# canbus-nic.net
KiCad netlist of a schematic drawn in EAGLE
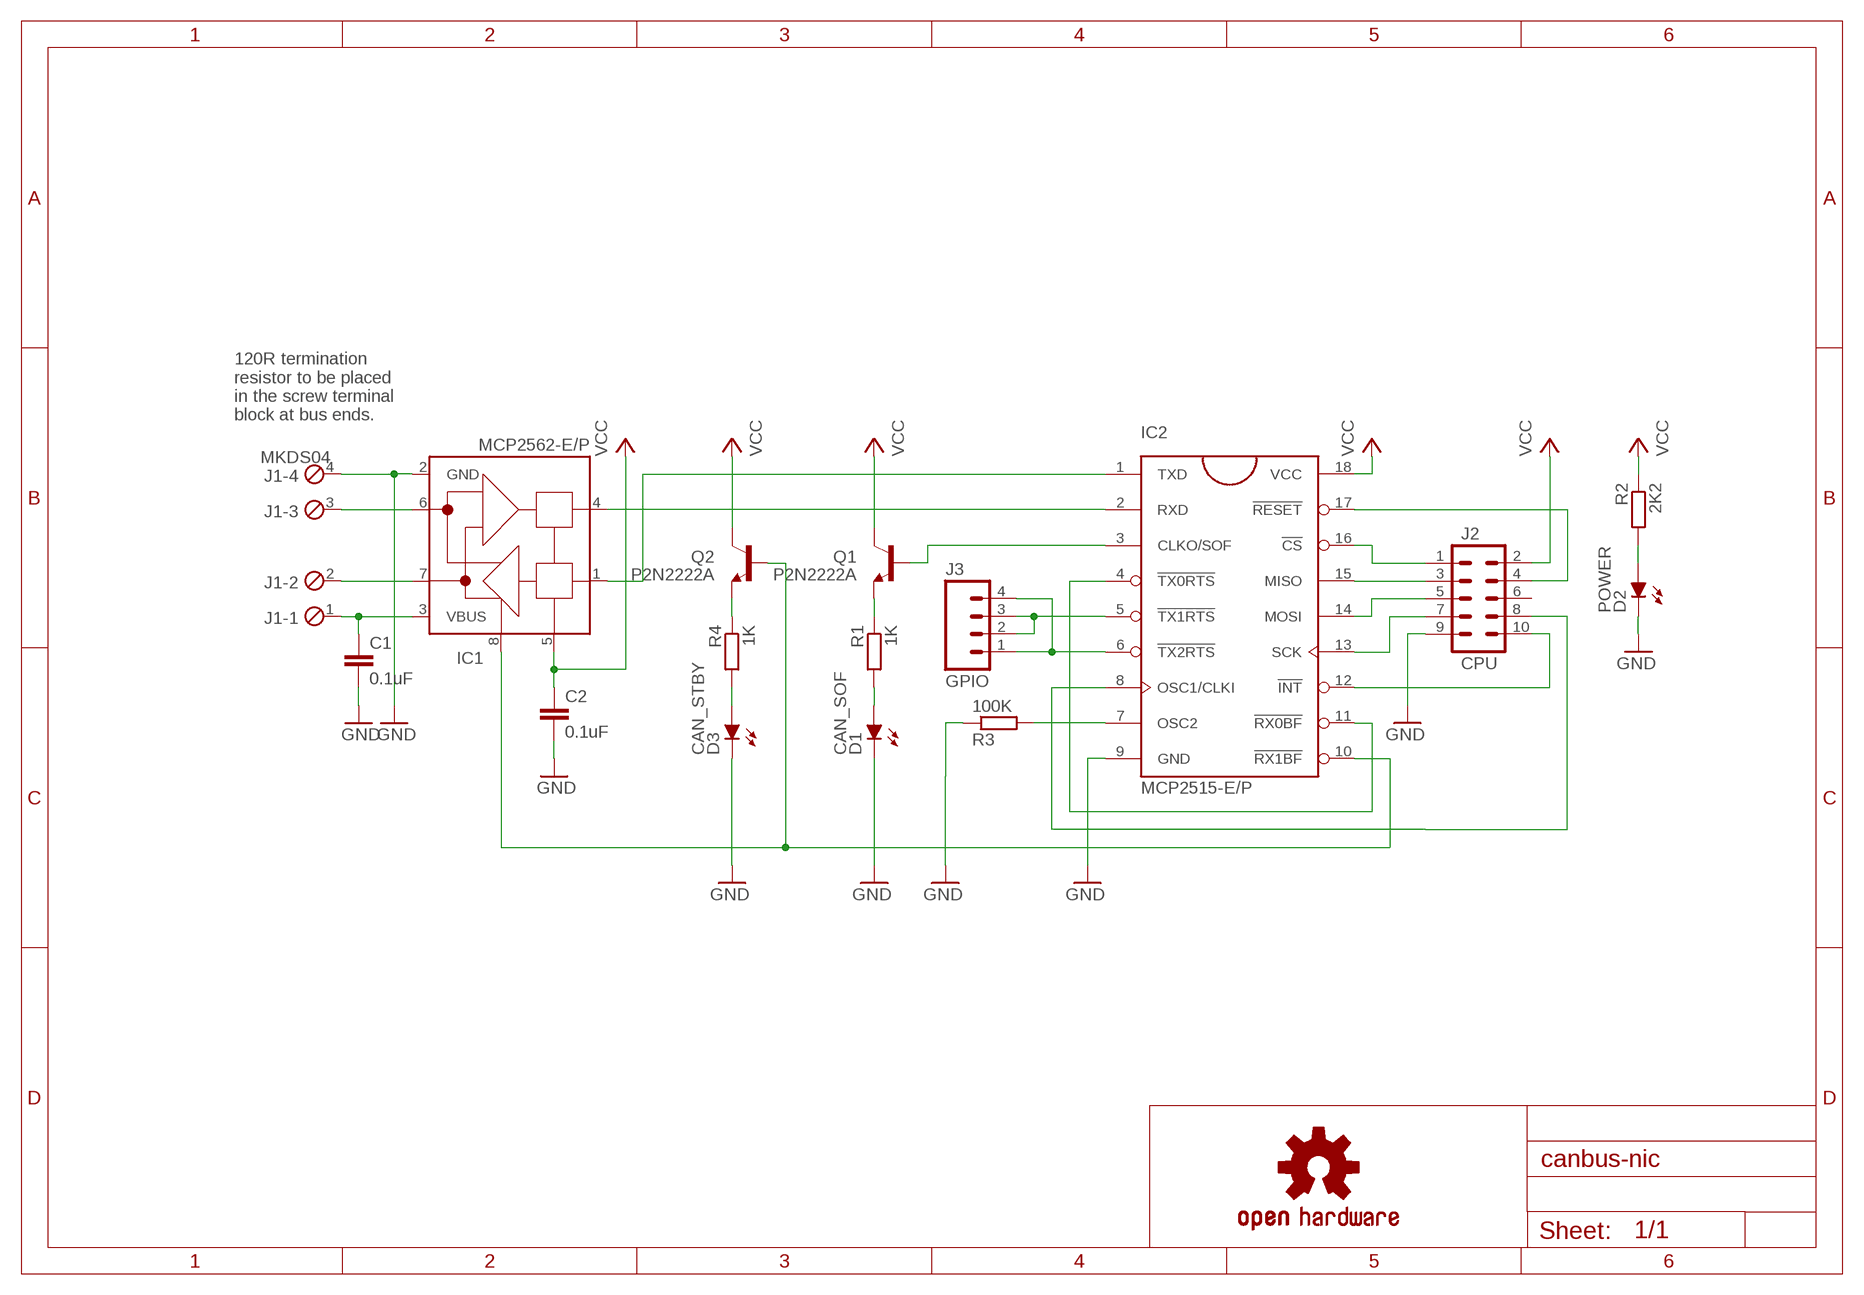
[diagram p0: schematic, sheet 1]

(export (version "E")
  (design (tool "Eeschema 10.0.6"))
  (components
    (comp (ref "C1")
      (value "0.1uF")
      (footprint "eagle-import:C050-025X075")
      (libsource (lib "eagle-import") (part "C-EU050-025X075"))
    )
    (comp (ref "C2")
      (value "0.1uF")
      (footprint "eagle-import:C050-025X075")
      (libsource (lib "eagle-import") (part "C-EU050-025X075"))
    )
    (comp (ref "D1")
      (value "CAN_SOF")
      (footprint "eagle-import:LED3MM")
      (libsource (lib "eagle-import") (part "LED3MM"))
    )
    (comp (ref "D2")
      (value "POWER")
      (footprint "eagle-import:LED3MM")
      (libsource (lib "eagle-import") (part "LED3MM"))
    )
    (comp (ref "D3")
      (value "CAN_STBY")
      (footprint "eagle-import:LED3MM")
      (libsource (lib "eagle-import") (part "LED3MM"))
    )
    (comp (ref "IC1")
      (value "MCP2562-E/P")
      (footprint "eagle-import:DIL08")
      (libsource (lib "eagle-import") (part "MCP2562-/PE"))
    )
    (comp (ref "IC2")
      (value "MCP2515-E/P")
      (footprint "eagle-import:DIL18")
      (libsource (lib "eagle-import") (part "MCP2515-/PE"))
    )
    (comp (ref "J1")
      (value "MKDS04")
      (footprint "eagle-import:MKDS04")
      (libsource (lib "eagle-import") (part "MKDS04"))
    )
    (comp (ref "J2")
      (value "CPU")
      (footprint "eagle-import:2X5-SHROUDED")
      (libsource (lib "eagle-import") (part "M05X2SHD"))
    )
    (comp (ref "J3")
      (value "GPIO")
      (footprint "eagle-import:1X04")
      (libsource (lib "eagle-import") (part "M04PTH"))
    )
    (comp (ref "LOGO1")
      (value "OSHW-LOGOMINI")
      (footprint "eagle-import:OSHW-LOGO-MINI")
      (libsource (lib "eagle-import") (part "OSHW-LOGOMINI"))
    )
    (comp (ref "Q1")
      (value "P2N2222A")
      (footprint "eagle-import:TO92")
      (libsource (lib "eagle-import") (part "P2N2222A"))
    )
    (comp (ref "Q2")
      (value "P2N2222A")
      (footprint "eagle-import:TO92")
      (libsource (lib "eagle-import") (part "P2N2222A"))
    )
    (comp (ref "R1")
      (value "1K")
      (footprint "eagle-import:0207_5V")
      (libsource (lib "eagle-import") (part "R-EU_0207/5V"))
    )
    (comp (ref "R2")
      (value "2K2")
      (footprint "eagle-import:0207_5V")
      (libsource (lib "eagle-import") (part "R-EU_0207/5V"))
    )
    (comp (ref "R3")
      (value "100K")
      (footprint "eagle-import:0207_5V")
      (libsource (lib "eagle-import") (part "R-EU_0207/5V"))
    )
    (comp (ref "R4")
      (value "1K")
      (footprint "eagle-import:0207_5V")
      (libsource (lib "eagle-import") (part "R-EU_0207/5V"))
    )
  )
  (nets
    (net (code "1") (name "GND") (class "Default")
      (node (ref "C1") (pin "2") (pinfunction "2_2") (pintype "passive"))
      (node (ref "C2") (pin "2") (pinfunction "2_2") (pintype "passive"))
      (node (ref "D1") (pin "K") (pinfunction "C_K") (pintype "passive"))
      (node (ref "D2") (pin "K") (pinfunction "C_K") (pintype "passive"))
      (node (ref "D3") (pin "K") (pinfunction "C_K") (pintype "passive"))
      (node (ref "IC1") (pin "2") (pinfunction "GND_2") (pintype "power_in"))
      (node (ref "IC2") (pin "9") (pinfunction "GND_9") (pintype "power_in"))
      (node (ref "J1") (pin "4") (pinfunction "1_4") (pintype "passive"))
      (node (ref "J2") (pin "9") (pinfunction "9_9") (pintype "passive"))
      (node (ref "R3") (pin "1") (pinfunction "1_1") (pintype "passive"))
    )
    (net (code "2") (name "Net-(D1-PadA)") (class "Default")
      (node (ref "D1") (pin "A") (pinfunction "A_A") (pintype "passive"))
      (node (ref "R1") (pin "2") (pinfunction "2_2") (pintype "passive"))
    )
    (net (code "3") (name "Net-(D2-PadA)") (class "Default")
      (node (ref "D2") (pin "A") (pinfunction "A_A") (pintype "passive"))
      (node (ref "R2") (pin "2") (pinfunction "2_2") (pintype "passive"))
    )
    (net (code "4") (name "Net-(D3-PadA)") (class "Default")
      (node (ref "D3") (pin "A") (pinfunction "A_A") (pintype "passive"))
      (node (ref "R4") (pin "2") (pinfunction "2_2") (pintype "passive"))
    )
    (net (code "5") (name "Net-(IC1-CANH)") (class "Default")
      (node (ref "IC1") (pin "7") (pinfunction "CANH_7") (pintype "bidirectional"))
      (node (ref "J1") (pin "2") (pinfunction "1_2") (pintype "passive"))
    )
    (net (code "6") (name "Net-(IC1-CANL)") (class "Default")
      (node (ref "IC1") (pin "6") (pinfunction "CANL_6") (pintype "bidirectional"))
      (node (ref "J1") (pin "3") (pinfunction "1_3") (pintype "passive"))
    )
    (net (code "7") (name "Net-(IC1-RXD)") (class "Default")
      (node (ref "IC1") (pin "4") (pinfunction "RXD_4") (pintype "output"))
      (node (ref "IC2") (pin "2") (pinfunction "RXD_2") (pintype "input"))
    )
    (net (code "8") (name "Net-(IC1-STBY)") (class "Default")
      (node (ref "IC1") (pin "8") (pinfunction "STBY_8") (pintype "input"))
      (node (ref "IC2") (pin "10") (pinfunction "~{RX1BF}_10") (pintype "output"))
      (node (ref "Q2") (pin "2") (pinfunction "B_2") (pintype "passive"))
    )
    (net (code "9") (name "Net-(IC1-TXD)") (class "Default")
      (node (ref "IC1") (pin "1") (pinfunction "TXD_1") (pintype "input"))
      (node (ref "IC2") (pin "1") (pinfunction "TXD_1") (pintype "output"))
    )
    (net (code "10") (name "Net-(IC1-VBUS)") (class "Default")
      (node (ref "C1") (pin "1") (pinfunction "1_1") (pintype "passive"))
      (node (ref "IC1") (pin "3") (pinfunction "VBUS_3") (pintype "power_in"))
      (node (ref "J1") (pin "1") (pinfunction "1_1") (pintype "passive"))
    )
    (net (code "11") (name "Net-(IC2-CLKO{slash}SOF)") (class "Default")
      (node (ref "IC2") (pin "3") (pinfunction "CLKO/SOF_3") (pintype "output"))
      (node (ref "Q1") (pin "2") (pinfunction "B_2") (pintype "passive"))
    )
    (net (code "12") (name "Net-(IC2-MISO)") (class "Default")
      (node (ref "IC2") (pin "15") (pinfunction "MISO_15") (pintype "output"))
      (node (ref "J2") (pin "3") (pinfunction "3_3") (pintype "passive"))
    )
    (net (code "13") (name "Net-(IC2-MOSI)") (class "Default")
      (node (ref "IC2") (pin "14") (pinfunction "MOSI_14") (pintype "input"))
      (node (ref "J2") (pin "5") (pinfunction "5_5") (pintype "passive"))
    )
    (net (code "14") (name "Net-(IC2-OSC1{slash}CLKI)") (class "Default")
      (node (ref "IC2") (pin "8") (pinfunction "OSC1/CLKI_8") (pintype "passive"))
      (node (ref "J2") (pin "8") (pinfunction "8_8") (pintype "passive"))
    )
    (net (code "15") (name "Net-(IC2-OSC2)") (class "Default")
      (node (ref "IC2") (pin "7") (pinfunction "OSC2_7") (pintype "passive"))
      (node (ref "R3") (pin "2") (pinfunction "2_2") (pintype "passive"))
    )
    (net (code "16") (name "Net-(IC2-SCK)") (class "Default")
      (node (ref "IC2") (pin "13") (pinfunction "SCK_13") (pintype "input"))
      (node (ref "J2") (pin "7") (pinfunction "7_7") (pintype "passive"))
    )
    (net (code "17") (name "Net-(IC2-~{CS})") (class "Default")
      (node (ref "IC2") (pin "16") (pinfunction "~{CS}_16") (pintype "input"))
      (node (ref "J2") (pin "1") (pinfunction "1_1") (pintype "passive"))
    )
    (net (code "18") (name "Net-(IC2-~{INT})") (class "Default")
      (node (ref "IC2") (pin "12") (pinfunction "~{INT}_12") (pintype "output"))
      (node (ref "J2") (pin "10") (pinfunction "10_10") (pintype "passive"))
    )
    (net (code "19") (name "Net-(IC2-~{RESET})") (class "Default")
      (node (ref "IC2") (pin "17") (pinfunction "~{RESET}_17") (pintype "input"))
      (node (ref "J2") (pin "4") (pinfunction "4_4") (pintype "passive"))
    )
    (net (code "20") (name "Net-(IC2-~{RX0BF})") (class "Default")
      (node (ref "IC2") (pin "11") (pinfunction "~{RX0BF}_11") (pintype "output"))
      (node (ref "IC2") (pin "4") (pinfunction "~{TX0RTS}_4") (pintype "input"))
    )
    (net (code "21") (name "Net-(IC2-~{TX1RTS})") (class "Default")
      (node (ref "IC2") (pin "5") (pinfunction "~{TX1RTS}_5") (pintype "input"))
      (node (ref "J3") (pin "2") (pinfunction "2_2") (pintype "passive"))
      (node (ref "J3") (pin "3") (pinfunction "3_3") (pintype "passive"))
    )
    (net (code "22") (name "Net-(IC2-~{TX2RTS})") (class "Default")
      (node (ref "IC2") (pin "6") (pinfunction "~{TX2RTS}_6") (pintype "input"))
      (node (ref "J3") (pin "1") (pinfunction "1_1") (pintype "passive"))
      (node (ref "J3") (pin "4") (pinfunction "4_4") (pintype "passive"))
    )
    (net (code "23") (name "Net-(Q1-E)") (class "Default")
      (node (ref "Q1") (pin "1") (pinfunction "E_1") (pintype "passive"))
      (node (ref "R1") (pin "1") (pinfunction "1_1") (pintype "passive"))
    )
    (net (code "24") (name "Net-(Q2-E)") (class "Default")
      (node (ref "Q2") (pin "1") (pinfunction "E_1") (pintype "passive"))
      (node (ref "R4") (pin "1") (pinfunction "1_1") (pintype "passive"))
    )
    (net (code "25") (name "VCC") (class "Default")
      (node (ref "C2") (pin "1") (pinfunction "1_1") (pintype "passive"))
      (node (ref "IC1") (pin "5") (pinfunction "VCC_5") (pintype "power_in"))
      (node (ref "IC2") (pin "18") (pinfunction "VCC_18") (pintype "power_in"))
      (node (ref "J2") (pin "2") (pinfunction "2_2") (pintype "passive"))
      (node (ref "Q1") (pin "3") (pinfunction "C_3") (pintype "passive"))
      (node (ref "Q2") (pin "3") (pinfunction "C_3") (pintype "passive"))
      (node (ref "R2") (pin "1") (pinfunction "1_1") (pintype "passive"))
    )
    (net (code "26") (name "unconnected-(J2-Pad6)") (class "Default")
      (node (ref "J2") (pin "6") (pinfunction "6_6") (pintype "passive"))
    )
  )
)
